# Cape_Overview.net
KiCad netlist of a schematic drawn in Altium Designer
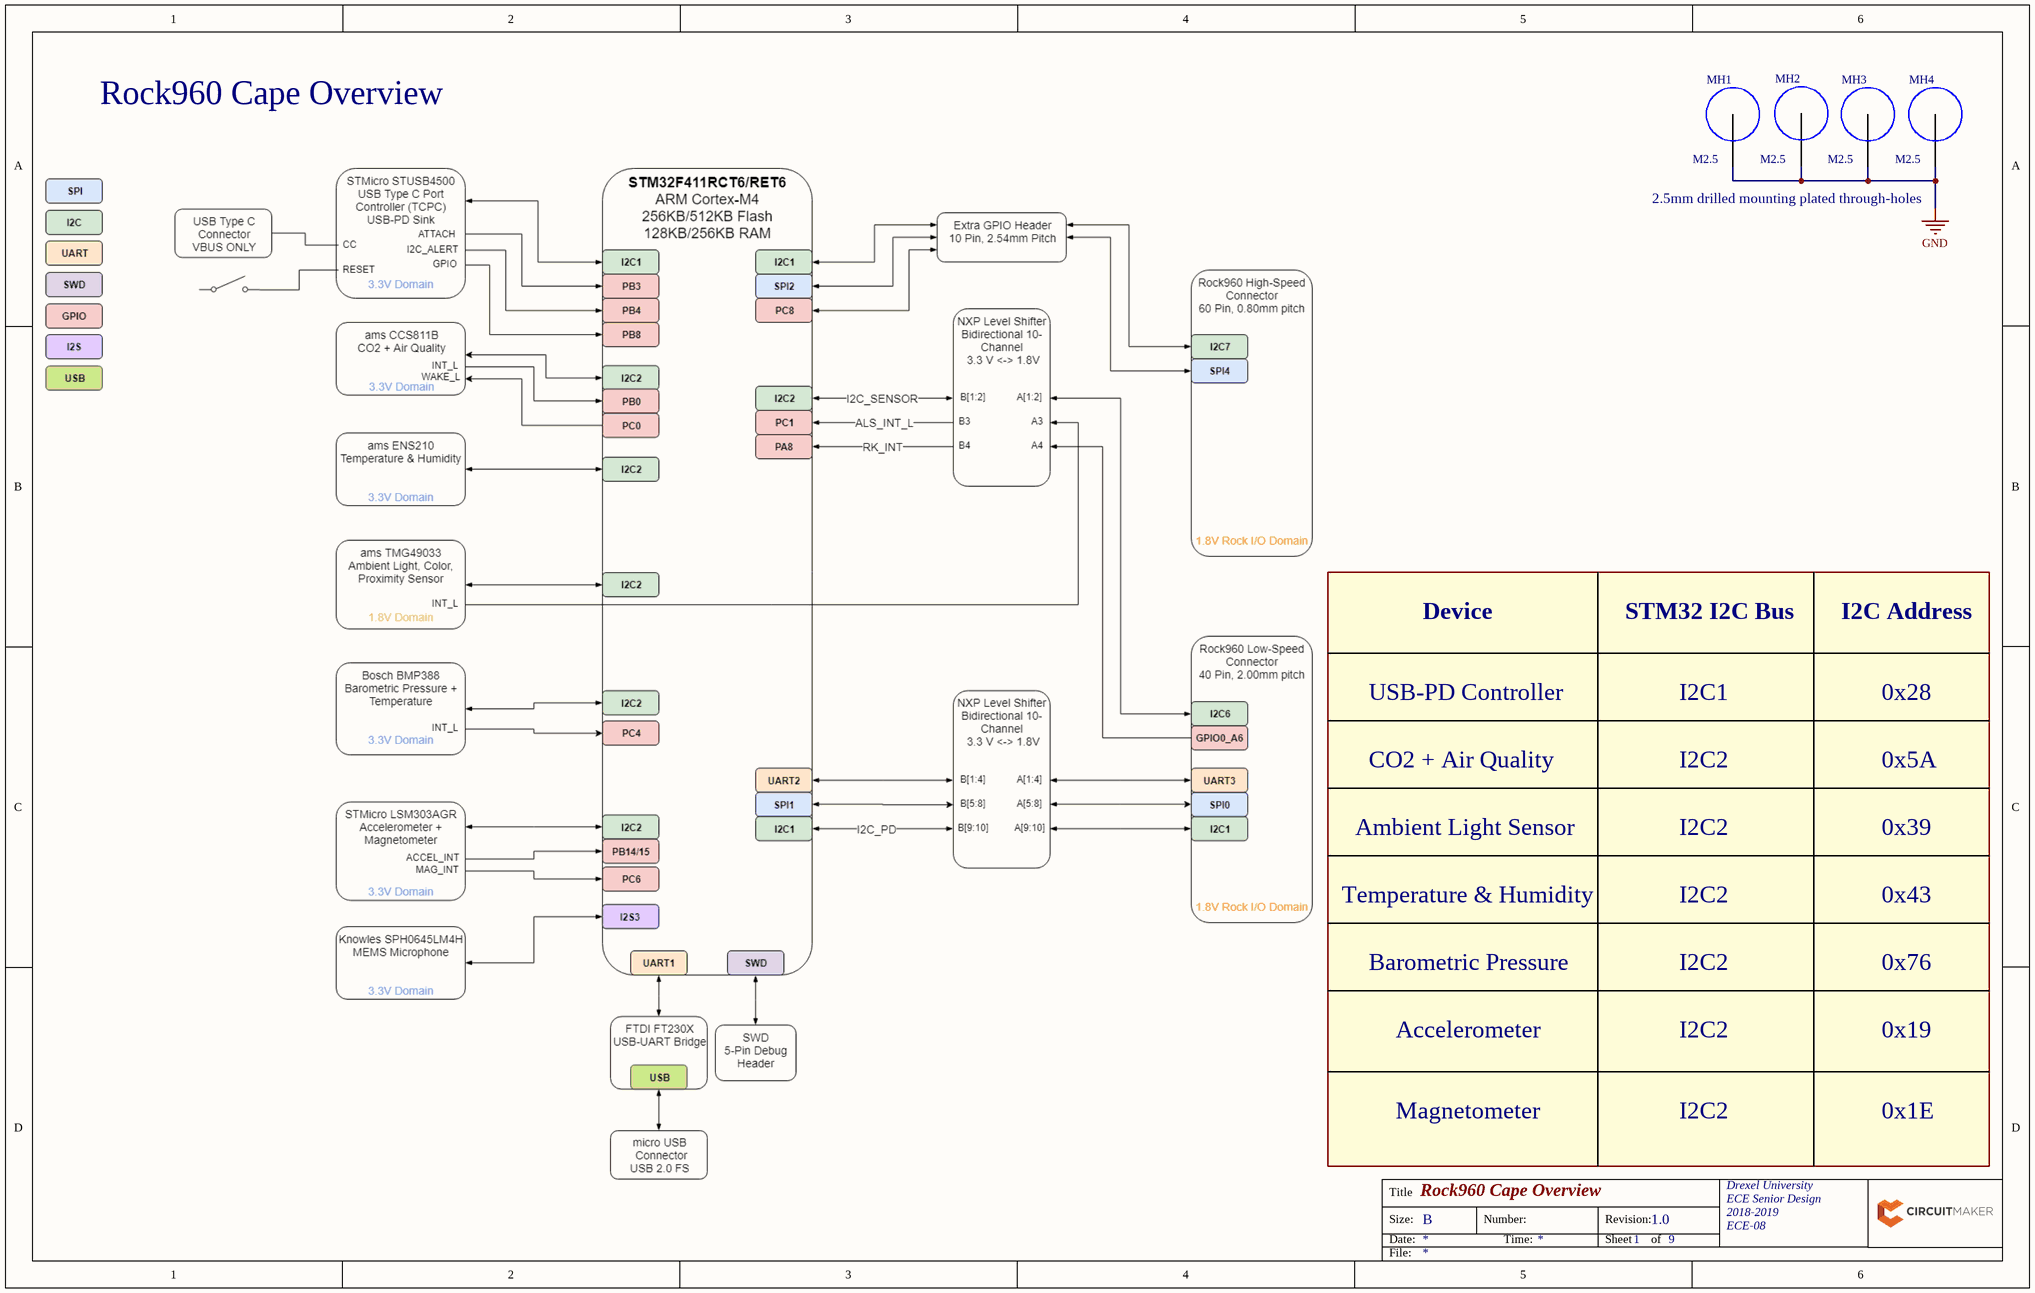
[diagram p0: Cape Overview.SchDoc]

(export (version "E")
  (design (tool "Eeschema 10.0.6"))
  (components
    (comp (ref "MH1")
      (value "M2.5")
      (footprint "PCB-cs3sr3addcss8sioosoo-1")
      (description "Plated Through-Hole Mechanical, 2.5mm drilled, 5.0mm diameter")
      (libsource (lib "CommunityVault") (part "CMP-yzeggvgux1nyfm6m4i34-1"))
    )
    (comp (ref "MH2")
      (value "M2.5")
      (footprint "PCB-cs3sr3addcss8sioosoo-1")
      (description "Plated Through-Hole Mechanical, 2.5mm drilled, 5.0mm diameter")
      (libsource (lib "CommunityVault") (part "CMP-yzeggvgux1nyfm6m4i34-1"))
    )
    (comp (ref "MH3")
      (value "M2.5")
      (footprint "PCB-cs3sr3addcss8sioosoo-1")
      (description "Plated Through-Hole Mechanical, 2.5mm drilled, 5.0mm diameter")
      (libsource (lib "FavoritesLibrary") (part "SYM-yzeggvgux1nyfm6m4i34-1"))
    )
    (comp (ref "MH4")
      (value "M2.5")
      (footprint "PCB-cs3sr3addcss8sioosoo-1")
      (description "Plated Through-Hole Mechanical, 2.5mm drilled, 5.0mm diameter")
      (libsource (lib "FavoritesLibrary") (part "SYM-yzeggvgux1nyfm6m4i34-1"))
    )
  )
  (nets
    (net (code "1") (name "GND") (class "Default")
      (node (ref "MH1") (pin "1") (pinfunction "1_1") (pintype "passive"))
      (node (ref "MH2") (pin "1") (pinfunction "1_1") (pintype "passive"))
      (node (ref "MH3") (pin "1") (pinfunction "1_1") (pintype "passive"))
      (node (ref "MH4") (pin "1") (pinfunction "1_1") (pintype "passive"))
    )
  )
)
